# wireless_interface.net
KiCad netlist of a schematic drawn in EAGLE
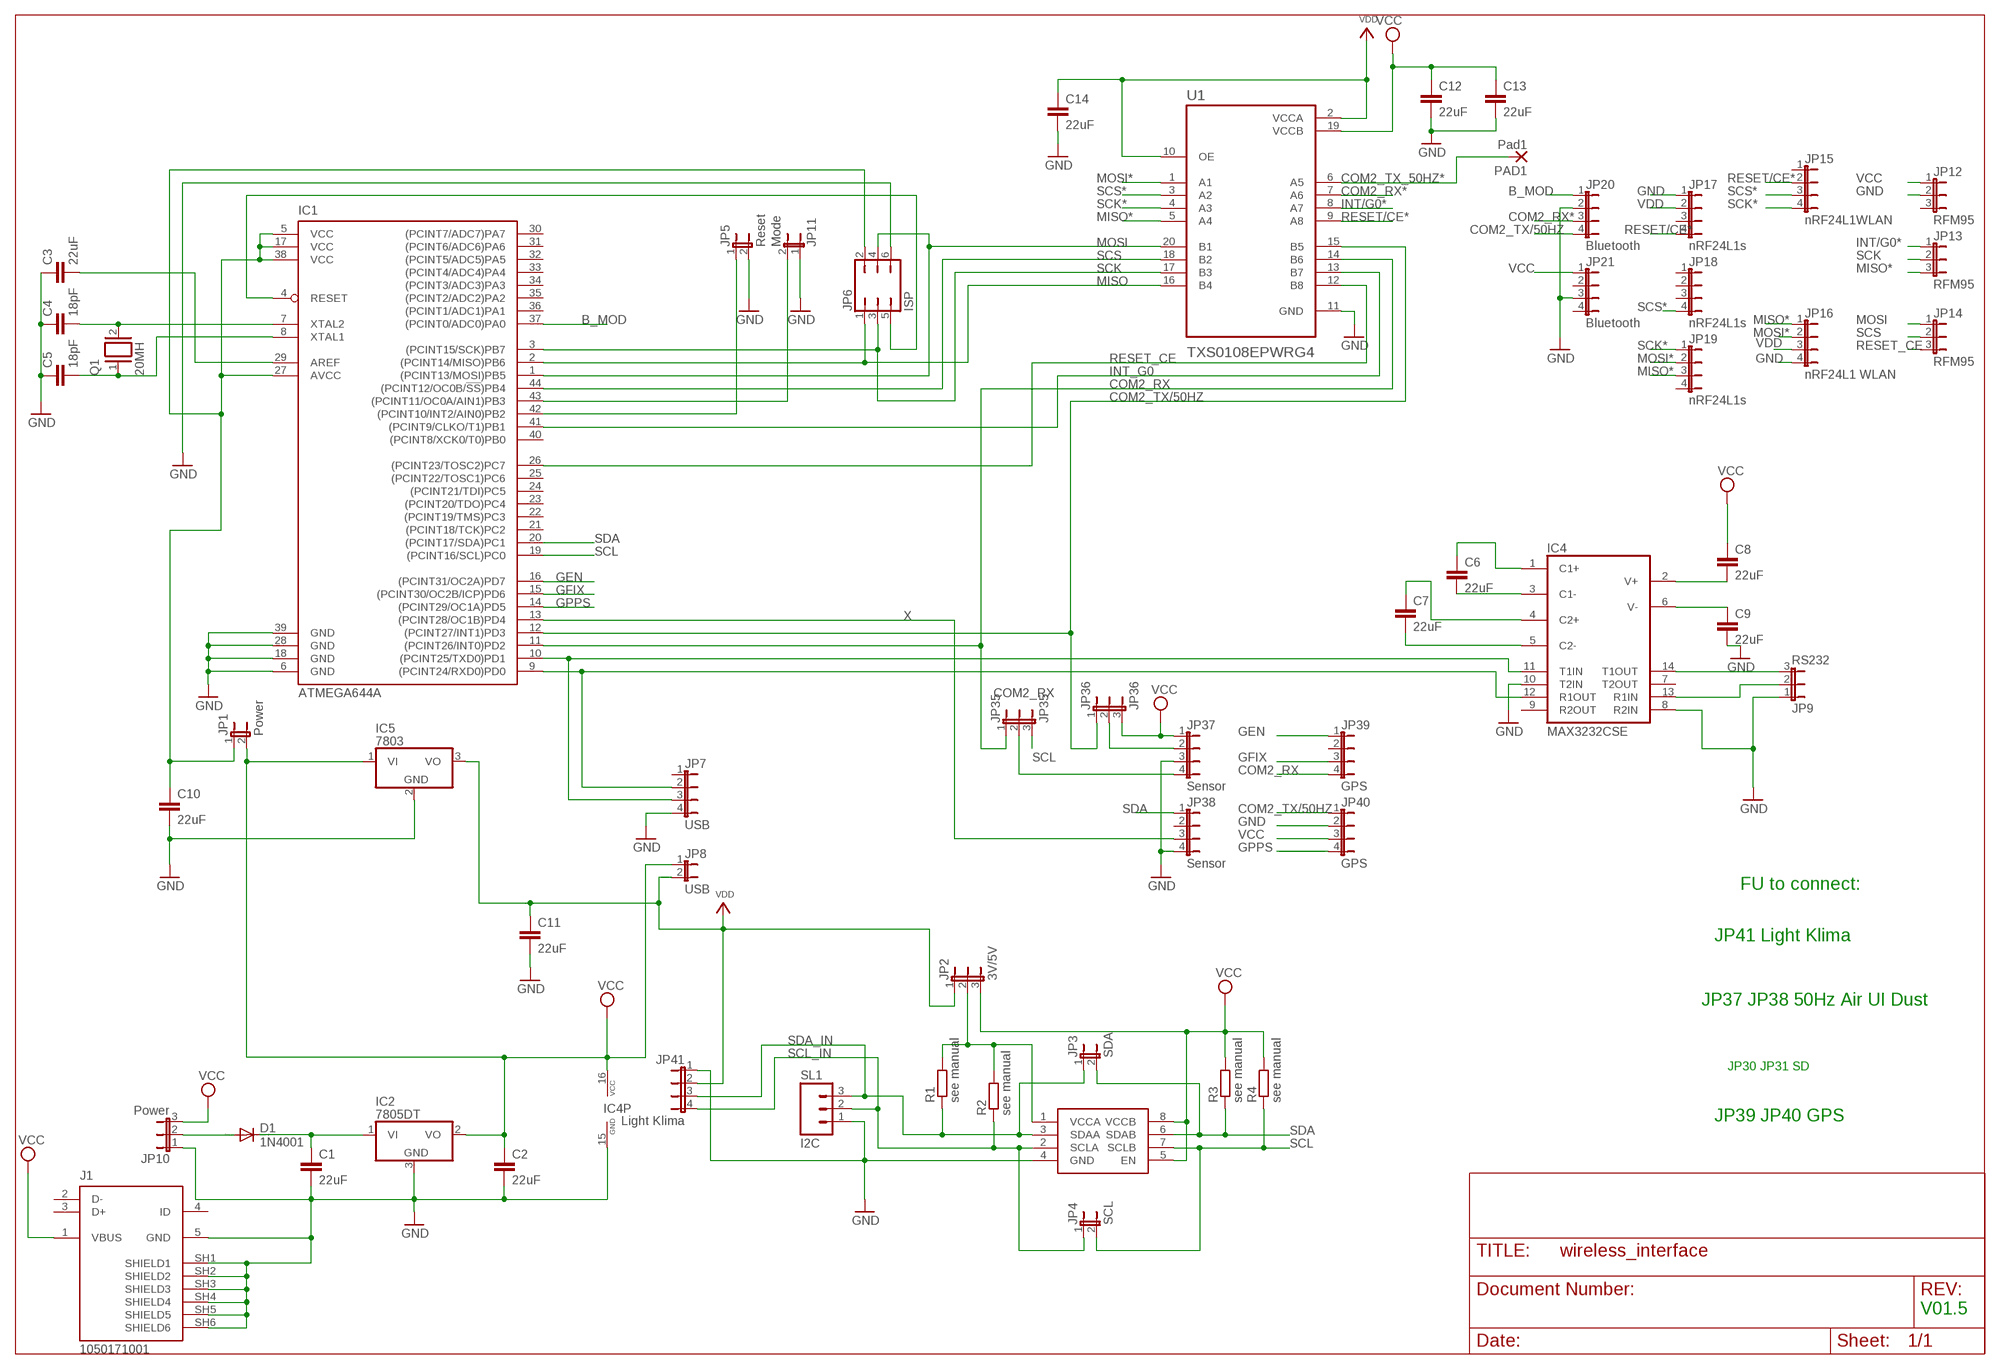
[diagram p0: schematic, sheet 1]

(export (version "E")
  (design (tool "Eeschema 10.0.6"))
  (components
    (comp (ref "C1")
      (value "22uF")
      (footprint "eagle-import:C1206")
      (libsource (lib "eagle-import") (part "C-EUC1206"))
    )
    (comp (ref "C2")
      (value "22uF")
      (footprint "eagle-import:C1206")
      (libsource (lib "eagle-import") (part "C-EUC1206"))
    )
    (comp (ref "C3")
      (value "22uF")
      (footprint "eagle-import:C1206")
      (libsource (lib "eagle-import") (part "C-EUC1206"))
    )
    (comp (ref "C4")
      (value "18pF")
      (footprint "eagle-import:C025-025X050")
      (libsource (lib "eagle-import") (part "resistor_C-EU025-025X050"))
    )
    (comp (ref "C5")
      (value "18pF")
      (footprint "eagle-import:C025-025X050")
      (libsource (lib "eagle-import") (part "resistor_C-EU025-025X050"))
    )
    (comp (ref "C6")
      (value "22uF")
      (footprint "eagle-import:C1206")
      (libsource (lib "eagle-import") (part "C-EUC1206"))
    )
    (comp (ref "C7")
      (value "22uF")
      (footprint "eagle-import:C1206")
      (libsource (lib "eagle-import") (part "C-EUC1206"))
    )
    (comp (ref "C8")
      (value "22uF")
      (footprint "eagle-import:C1206")
      (libsource (lib "eagle-import") (part "C-EUC1206"))
    )
    (comp (ref "C9")
      (value "22uF")
      (footprint "eagle-import:C1206")
      (libsource (lib "eagle-import") (part "C-EUC1206"))
    )
    (comp (ref "C10")
      (value "22uF")
      (footprint "eagle-import:C1206")
      (libsource (lib "eagle-import") (part "C-EUC1206"))
    )
    (comp (ref "C11")
      (value "22uF")
      (footprint "eagle-import:C1206")
      (libsource (lib "eagle-import") (part "C-EUC1206"))
    )
    (comp (ref "C12")
      (value "22uF")
      (footprint "eagle-import:C1206")
      (libsource (lib "eagle-import") (part "C-EUC1206"))
    )
    (comp (ref "C13")
      (value "22uF")
      (footprint "eagle-import:C1206")
      (libsource (lib "eagle-import") (part "C-EUC1206"))
    )
    (comp (ref "C14")
      (value "22uF")
      (footprint "eagle-import:C1206")
      (libsource (lib "eagle-import") (part "C-EUC1206"))
    )
    (comp (ref "D1")
      (value "1N4001")
      (footprint "eagle-import:SOD106-W")
      (libsource (lib "eagle-import") (part "DIODE-SOD106-W"))
    )
    (comp (ref "IC1")
      (value "ATMEGA644A")
      (footprint "eagle-import:TQFP44")
      (fields (field (name "MPN") "ATMEGA644PV-10AU"))
      (libsource (lib "eagle-import") (part "ATMEGA644A"))
    )
    (comp (ref "IC2")
      (value "7805DT")
      (footprint "eagle-import:TO252")
      (libsource (lib "eagle-import") (part "78DT05"))
    )
    (comp (ref "IC3")
      (value "PCA9517")
      (footprint "eagle-import:SO-08")
      (libsource (lib "eagle-import") (part "PCA9517"))
    )
    (comp (ref "IC4")
      (value "MAX3232CSE")
      (footprint "eagle-import:SO16")
      (libsource (lib "eagle-import") (part "MAX3232SEC"))
    )
    (comp (ref "IC5")
      (value "7803")
      (footprint "eagle-import:TO220V")
      (libsource (lib "eagle-import") (part "78TV05"))
    )
    (comp (ref "J1")
      (value "1050171001")
      (footprint "eagle-import:MOLEX_1050171001")
      (fields (field (name "MF") "Molex"))
      (libsource (lib "eagle-import") (part "1050171001"))
    )
    (comp (ref "JP1")
      (value "Power")
      (footprint "eagle-import:JP1")
      (libsource (lib "eagle-import") (part "JP1E"))
    )
    (comp (ref "JP2")
      (value "3V/5V")
      (footprint "eagle-import:JP2")
      (libsource (lib "eagle-import") (part "JP2E"))
    )
    (comp (ref "JP3")
      (value "SDA")
      (footprint "eagle-import:JP1")
      (libsource (lib "eagle-import") (part "JP1E"))
    )
    (comp (ref "JP4")
      (value "SCL")
      (footprint "eagle-import:JP1")
      (libsource (lib "eagle-import") (part "JP1E"))
    )
    (comp (ref "JP5")
      (value "Reset")
      (footprint "eagle-import:JP1")
      (libsource (lib "eagle-import") (part "JP1E"))
    )
    (comp (ref "JP6")
      (value "ISP")
      (footprint "eagle-import:JP3Q")
      (libsource (lib "eagle-import") (part "JP3Q"))
    )
    (comp (ref "JP7")
      (value "USB")
      (footprint "eagle-import:JP4")
      (libsource (lib "eagle-import") (part "JP4E"))
    )
    (comp (ref "JP8")
      (value "USB")
      (footprint "eagle-import:JP1")
      (libsource (lib "eagle-import") (part "JP1E"))
    )
    (comp (ref "JP9")
      (value "RS232")
      (footprint "eagle-import:JP2")
      (libsource (lib "eagle-import") (part "JP2E"))
    )
    (comp (ref "JP10")
      (value "Power")
      (footprint "eagle-import:JP2")
      (libsource (lib "eagle-import") (part "JP2E"))
    )
    (comp (ref "JP11")
      (value "Mode")
      (footprint "eagle-import:JP1")
      (libsource (lib "eagle-import") (part "JP1E"))
    )
    (comp (ref "JP12")
      (value "RFM95")
      (footprint "eagle-import:JP2")
      (libsource (lib "eagle-import") (part "JP2E"))
    )
    (comp (ref "JP13")
      (value "RFM95")
      (footprint "eagle-import:JP2")
      (libsource (lib "eagle-import") (part "JP2E"))
    )
    (comp (ref "JP14")
      (value "RFM95")
      (footprint "eagle-import:JP2")
      (libsource (lib "eagle-import") (part "JP2E"))
    )
    (comp (ref "JP15")
      (value "nRF24L1WLAN")
      (footprint "eagle-import:JP4")
      (libsource (lib "eagle-import") (part "JP4E"))
    )
    (comp (ref "JP16")
      (value "nRF24L1 WLAN")
      (footprint "eagle-import:JP4")
      (libsource (lib "eagle-import") (part "JP4E"))
    )
    (comp (ref "JP17")
      (value "nRF24L1s")
      (footprint "eagle-import:JP4")
      (libsource (lib "eagle-import") (part "JP4E"))
    )
    (comp (ref "JP18")
      (value "nRF24L1s")
      (footprint "eagle-import:JP4")
      (libsource (lib "eagle-import") (part "JP4E"))
    )
    (comp (ref "JP19")
      (value "nRF24L1s")
      (footprint "eagle-import:JP4")
      (libsource (lib "eagle-import") (part "JP4E"))
    )
    (comp (ref "JP20")
      (value "Bluetooth")
      (footprint "eagle-import:JP4")
      (libsource (lib "eagle-import") (part "JP4E"))
    )
    (comp (ref "JP21")
      (value "Bluetooth")
      (footprint "eagle-import:JP4")
      (libsource (lib "eagle-import") (part "JP4E"))
    )
    (comp (ref "JP35")
      (value "JP35")
      (footprint "eagle-import:JP2")
      (libsource (lib "eagle-import") (part "JP2E"))
    )
    (comp (ref "JP36")
      (value "JP36")
      (footprint "eagle-import:JP2")
      (libsource (lib "eagle-import") (part "JP2E"))
    )
    (comp (ref "JP37")
      (value "Sensor")
      (footprint "eagle-import:JP4")
      (libsource (lib "eagle-import") (part "JP4E"))
    )
    (comp (ref "JP38")
      (value "Sensor")
      (footprint "eagle-import:JP4")
      (libsource (lib "eagle-import") (part "JP4E"))
    )
    (comp (ref "JP39")
      (value "GPS")
      (footprint "eagle-import:JP4")
      (libsource (lib "eagle-import") (part "JP4E"))
    )
    (comp (ref "JP40")
      (value "GPS")
      (footprint "eagle-import:JP4")
      (libsource (lib "eagle-import") (part "JP4E"))
    )
    (comp (ref "JP41")
      (value "Light Klima")
      (footprint "eagle-import:JP4")
      (libsource (lib "eagle-import") (part "JP4E"))
    )
    (comp (ref "PAD1")
      (value "Pad1")
      (footprint "eagle-import:SMD1,27-2,54")
      (libsource (lib "eagle-import") (part "WIREPADSMD1,27-254"))
    )
    (comp (ref "Q1")
      (value "20MH")
      (footprint "eagle-import:QS")
      (libsource (lib "eagle-import") (part "XTAL/S"))
    )
    (comp (ref "R1")
      (value "see manual")
      (footprint "eagle-import:R1206")
      (libsource (lib "eagle-import") (part "R-EU_R1206"))
    )
    (comp (ref "R2")
      (value "see manual")
      (footprint "eagle-import:R1206")
      (libsource (lib "eagle-import") (part "R-EU_R1206"))
    )
    (comp (ref "R3")
      (value "see manual")
      (footprint "eagle-import:R1206")
      (libsource (lib "eagle-import") (part "R-EU_R1206"))
    )
    (comp (ref "R4")
      (value "see manual")
      (footprint "eagle-import:R1206")
      (libsource (lib "eagle-import") (part "R-EU_R1206"))
    )
    (comp (ref "SL1")
      (value "I2C")
      (footprint "eagle-import:03P")
      (libsource (lib "eagle-import") (part "M03"))
    )
    (comp (ref "U1")
      (value "TXS0108EPWRG4")
      (footprint "eagle-import:SOP65P640X120-20N")
      (fields (field (name "MF") "Texas Instruments"))
      (libsource (lib "eagle-import") (part "TXS0108EPWRG4"))
    )
  )
  (nets
    (net (code "1") (name "/B_MOD") (class "Default")
      (node (ref "IC1") (pin "37") (pinfunction "(PCINT0/ADC0)PA0_37") (pintype "bidirectional"))
      (node (ref "JP20") (pin "1") (pinfunction "1_1") (pintype "passive"))
    )
    (net (code "2") (name "/COM2_RX") (class "Default")
      (node (ref "IC1") (pin "11") (pinfunction "(PCINT26/INT0)PD2_11") (pintype "bidirectional"))
      (node (ref "JP35") (pin "1") (pinfunction "1_1") (pintype "passive"))
      (node (ref "JP39") (pin "4") (pinfunction "4_4") (pintype "passive"))
      (node (ref "U1") (pin "14") (pinfunction "B6_14") (pintype "bidirectional"))
    )
    (net (code "3") (name "/COM2_RX*") (class "Default")
      (node (ref "JP20") (pin "3") (pinfunction "3_3") (pintype "passive"))
      (node (ref "U1") (pin "7") (pinfunction "A6_7") (pintype "bidirectional"))
    )
    (net (code "4") (name "/COM2_TX_50HZ*") (class "Default")
      (node (ref "PAD1") (pin "1") (pinfunction "P_1") (pintype "passive"))
      (node (ref "U1") (pin "6") (pinfunction "A5_6") (pintype "bidirectional"))
    )
    (net (code "5") (name "/COM2_TX{slash}50HZ") (class "Default")
      (node (ref "IC1") (pin "12") (pinfunction "(PCINT27/INT1)PD3_12") (pintype "bidirectional"))
      (node (ref "JP20") (pin "4") (pinfunction "4_4") (pintype "passive"))
      (node (ref "JP36") (pin "1") (pinfunction "1_1") (pintype "passive"))
      (node (ref "JP40") (pin "1") (pinfunction "1_1") (pintype "passive"))
      (node (ref "U1") (pin "15") (pinfunction "B5_15") (pintype "bidirectional"))
    )
    (net (code "6") (name "/GEN") (class "Default")
      (node (ref "IC1") (pin "16") (pinfunction "(PCINT31/OC2A)PD7_16") (pintype "bidirectional"))
      (node (ref "JP39") (pin "1") (pinfunction "1_1") (pintype "passive"))
    )
    (net (code "7") (name "/GFIX") (class "Default")
      (node (ref "IC1") (pin "15") (pinfunction "(PCINT30/OC2B/ICP)PD6_15") (pintype "bidirectional"))
      (node (ref "JP39") (pin "3") (pinfunction "3_3") (pintype "passive"))
    )
    (net (code "8") (name "/GPPS") (class "Default")
      (node (ref "IC1") (pin "14") (pinfunction "(PCINT29/OC1A)PD5_14") (pintype "bidirectional"))
      (node (ref "JP40") (pin "4") (pinfunction "4_4") (pintype "passive"))
    )
    (net (code "9") (name "/INT_G0") (class "Default")
      (node (ref "IC1") (pin "41") (pinfunction "(PCINT9/CLKO/T1)PB1_41") (pintype "bidirectional"))
      (node (ref "U1") (pin "13") (pinfunction "B7_13") (pintype "bidirectional"))
    )
    (net (code "10") (name "/INT{slash}G0*") (class "Default")
      (node (ref "JP13") (pin "1") (pinfunction "1_1") (pintype "passive"))
      (node (ref "U1") (pin "8") (pinfunction "A7_8") (pintype "bidirectional"))
    )
    (net (code "11") (name "/MISO") (class "Default")
      (node (ref "IC1") (pin "2") (pinfunction "(PCINT14/MISO)PB6_2") (pintype "bidirectional"))
      (node (ref "JP6") (pin "1") (pinfunction "1_1") (pintype "passive"))
      (node (ref "U1") (pin "16") (pinfunction "B4_16") (pintype "bidirectional"))
    )
    (net (code "12") (name "/MISO*") (class "Default")
      (node (ref "JP13") (pin "3") (pinfunction "3_3") (pintype "passive"))
      (node (ref "JP16") (pin "1") (pinfunction "1_1") (pintype "passive"))
      (node (ref "JP19") (pin "3") (pinfunction "3_3") (pintype "passive"))
      (node (ref "U1") (pin "5") (pinfunction "A4_5") (pintype "bidirectional"))
    )
    (net (code "13") (name "/MOSI") (class "Default")
      (node (ref "IC1") (pin "1") (pinfunction "(PCINT13/MOSI)PB5_1") (pintype "bidirectional"))
      (node (ref "JP14") (pin "1") (pinfunction "1_1") (pintype "passive"))
      (node (ref "JP6") (pin "4") (pinfunction "4_4") (pintype "passive"))
      (node (ref "U1") (pin "20") (pinfunction "B1_20") (pintype "bidirectional"))
    )
    (net (code "14") (name "/MOSI*") (class "Default")
      (node (ref "JP16") (pin "2") (pinfunction "2_2") (pintype "passive"))
      (node (ref "JP19") (pin "2") (pinfunction "2_2") (pintype "passive"))
      (node (ref "U1") (pin "1") (pinfunction "A1_1") (pintype "bidirectional"))
    )
    (net (code "15") (name "/RESET_CE") (class "Default")
      (node (ref "IC1") (pin "26") (pinfunction "(PCINT23/TOSC2)PC7_26") (pintype "output"))
      (node (ref "JP14") (pin "3") (pinfunction "3_3") (pintype "passive"))
      (node (ref "U1") (pin "12") (pinfunction "B8_12") (pintype "bidirectional"))
    )
    (net (code "16") (name "/RESET{slash}CE*") (class "Default")
      (node (ref "JP15") (pin "2") (pinfunction "2_2") (pintype "passive"))
      (node (ref "JP17") (pin "4") (pinfunction "4_4") (pintype "passive"))
      (node (ref "U1") (pin "9") (pinfunction "A8_9") (pintype "bidirectional"))
    )
    (net (code "17") (name "/SCK") (class "Default")
      (node (ref "IC1") (pin "3") (pinfunction "(PCINT15/SCK)PB7_3") (pintype "bidirectional"))
      (node (ref "JP13") (pin "2") (pinfunction "2_2") (pintype "passive"))
      (node (ref "JP6") (pin "3") (pinfunction "3_3") (pintype "passive"))
      (node (ref "U1") (pin "17") (pinfunction "B3_17") (pintype "bidirectional"))
    )
    (net (code "18") (name "/SCK*") (class "Default")
      (node (ref "JP15") (pin "4") (pinfunction "4_4") (pintype "passive"))
      (node (ref "JP19") (pin "1") (pinfunction "1_1") (pintype "passive"))
      (node (ref "U1") (pin "4") (pinfunction "A3_4") (pintype "bidirectional"))
    )
    (net (code "19") (name "/SCL") (class "Default")
      (node (ref "IC1") (pin "19") (pinfunction "(PCINT16/SCL)PC0_19") (pintype "output"))
      (node (ref "IC3") (pin "7") (pinfunction "SCLB_7") (pintype "bidirectional"))
      (node (ref "JP35") (pin "3") (pinfunction "3_3") (pintype "passive"))
      (node (ref "JP4") (pin "2") (pinfunction "2_2") (pintype "passive"))
      (node (ref "R4") (pin "1") (pinfunction "1_1") (pintype "passive"))
    )
    (net (code "20") (name "/SCL_IN") (class "Default")
      (node (ref "IC3") (pin "2") (pinfunction "SCLA_2") (pintype "bidirectional"))
      (node (ref "JP4") (pin "1") (pinfunction "1_1") (pintype "passive"))
      (node (ref "JP41") (pin "4") (pinfunction "4_4") (pintype "passive"))
      (node (ref "R2") (pin "1") (pinfunction "1_1") (pintype "passive"))
      (node (ref "SL1") (pin "2") (pinfunction "2_2") (pintype "passive"))
    )
    (net (code "21") (name "/SCS") (class "Default")
      (node (ref "IC1") (pin "44") (pinfunction "(PCINT12/OC0B/~{SS})PB4_44") (pintype "bidirectional"))
      (node (ref "JP14") (pin "2") (pinfunction "2_2") (pintype "passive"))
      (node (ref "U1") (pin "18") (pinfunction "B2_18") (pintype "bidirectional"))
    )
    (net (code "22") (name "/SCS*") (class "Default")
      (node (ref "JP15") (pin "3") (pinfunction "3_3") (pintype "passive"))
      (node (ref "JP18") (pin "4") (pinfunction "4_4") (pintype "passive"))
      (node (ref "U1") (pin "3") (pinfunction "A2_3") (pintype "bidirectional"))
    )
    (net (code "23") (name "/SDA") (class "Default")
      (node (ref "IC1") (pin "20") (pinfunction "(PCINT17/SDA)PC1_20") (pintype "output"))
      (node (ref "IC3") (pin "6") (pinfunction "SDAB_6") (pintype "bidirectional"))
      (node (ref "JP3") (pin "2") (pinfunction "2_2") (pintype "passive"))
      (node (ref "JP38") (pin "1") (pinfunction "1_1") (pintype "passive"))
      (node (ref "R3") (pin "1") (pinfunction "1_1") (pintype "passive"))
    )
    (net (code "24") (name "/SDA_IN") (class "Default")
      (node (ref "IC3") (pin "3") (pinfunction "SDAA_3") (pintype "bidirectional"))
      (node (ref "JP3") (pin "1") (pinfunction "1_1") (pintype "passive"))
      (node (ref "JP41") (pin "3") (pinfunction "3_3") (pintype "passive"))
      (node (ref "R1") (pin "1") (pinfunction "1_1") (pintype "passive"))
      (node (ref "SL1") (pin "3") (pinfunction "3_3") (pintype "passive"))
    )
    (net (code "25") (name "/X") (class "Default")
      (node (ref "IC1") (pin "13") (pinfunction "(PCINT28/OC1B)PD4_13") (pintype "bidirectional"))
      (node (ref "JP38") (pin "3") (pinfunction "3_3") (pintype "passive"))
    )
    (net (code "26") (name "GND") (class "Default")
      (node (ref "C1") (pin "2") (pinfunction "2_2") (pintype "passive"))
      (node (ref "C10") (pin "2") (pinfunction "2_2") (pintype "passive"))
      (node (ref "C11") (pin "2") (pinfunction "2_2") (pintype "passive"))
      (node (ref "C12") (pin "2") (pinfunction "2_2") (pintype "passive"))
      (node (ref "C13") (pin "2") (pinfunction "2_2") (pintype "passive"))
      (node (ref "C14") (pin "2") (pinfunction "2_2") (pintype "passive"))
      (node (ref "C2") (pin "2") (pinfunction "2_2") (pintype "passive"))
      (node (ref "C3") (pin "1") (pinfunction "1_1") (pintype "passive"))
      (node (ref "C4") (pin "1") (pinfunction "1_1") (pintype "passive"))
      (node (ref "C5") (pin "1") (pinfunction "1_1") (pintype "passive"))
      (node (ref "C9") (pin "2") (pinfunction "2_2") (pintype "passive"))
      (node (ref "IC1") (pin "18") (pinfunction "GND_18") (pintype "power_in"))
      (node (ref "IC1") (pin "28") (pinfunction "GND_28") (pintype "power_in"))
      (node (ref "IC1") (pin "39") (pinfunction "GND_39") (pintype "power_in"))
      (node (ref "IC1") (pin "6") (pinfunction "GND_6") (pintype "power_in"))
      (node (ref "IC2") (pin "3") (pinfunction "GND_3") (pintype "passive"))
      (node (ref "IC3") (pin "4") (pinfunction "GND_4") (pintype "bidirectional"))
      (node (ref "IC4") (pin "10") (pinfunction "T2IN_10") (pintype "input"))
      (node (ref "IC4") (pin "15") (pinfunction "GND_15") (pintype "power_in"))
      (node (ref "IC4") (pin "8") (pinfunction "R2IN_8") (pintype "input"))
      (node (ref "IC5") (pin "2") (pinfunction "GND_2") (pintype "passive"))
      (node (ref "J1") (pin "5") (pinfunction "GND_5") (pintype "power_in"))
      (node (ref "J1") (pin "SH1") (pinfunction "SHIELD1_SH1") (pintype "passive"))
      (node (ref "J1") (pin "SH2") (pinfunction "SHIELD2_SH2") (pintype "passive"))
      (node (ref "J1") (pin "SH3") (pinfunction "SHIELD3_SH3") (pintype "passive"))
      (node (ref "J1") (pin "SH4") (pinfunction "SHIELD4_SH4") (pintype "passive"))
      (node (ref "J1") (pin "SH5") (pinfunction "SHIELD5_SH5") (pintype "passive"))
      (node (ref "J1") (pin "SH6") (pinfunction "SHIELD6_SH6") (pintype "passive"))
      (node (ref "JP10") (pin "1") (pinfunction "1_1") (pintype "passive"))
      (node (ref "JP11") (pin "1") (pinfunction "1_1") (pintype "passive"))
      (node (ref "JP12") (pin "2") (pinfunction "2_2") (pintype "passive"))
      (node (ref "JP16") (pin "4") (pinfunction "4_4") (pintype "passive"))
      (node (ref "JP17") (pin "1") (pinfunction "1_1") (pintype "passive"))
      (node (ref "JP20") (pin "2") (pinfunction "2_2") (pintype "passive"))
      (node (ref "JP21") (pin "3") (pinfunction "3_3") (pintype "passive"))
      (node (ref "JP37") (pin "3") (pinfunction "3_3") (pintype "passive"))
      (node (ref "JP38") (pin "4") (pinfunction "4_4") (pintype "passive"))
      (node (ref "JP40") (pin "2") (pinfunction "2_2") (pintype "passive"))
      (node (ref "JP41") (pin "1") (pinfunction "1_1") (pintype "passive"))
      (node (ref "JP5") (pin "2") (pinfunction "2_2") (pintype "passive"))
      (node (ref "JP6") (pin "6") (pinfunction "6_6") (pintype "passive"))
      (node (ref "JP7") (pin "4") (pinfunction "4_4") (pintype "passive"))
      (node (ref "JP9") (pin "1") (pinfunction "1_1") (pintype "passive"))
      (node (ref "SL1") (pin "1") (pinfunction "1_1") (pintype "passive"))
      (node (ref "U1") (pin "11") (pinfunction "GND_11") (pintype "power_in"))
    )
    (net (code "27") (name "Net-(D1-PadA)") (class "Default")
      (node (ref "D1") (pin "A") (pinfunction "A_A") (pintype "passive"))
      (node (ref "JP10") (pin "2") (pinfunction "2_2") (pintype "passive"))
    )
    (net (code "28") (name "Net-(IC1-(PCINT10{slash}INT2{slash}AIN0)PB2)") (class "Default")
      (node (ref "IC1") (pin "42") (pinfunction "(PCINT10/INT2/AIN0)PB2_42") (pintype "bidirectional"))
      (node (ref "JP5") (pin "1") (pinfunction "1_1") (pintype "passive"))
    )
    (net (code "29") (name "Net-(IC1-(PCINT11{slash}OC0A{slash}AIN1)PB3)") (class "Default")
      (node (ref "IC1") (pin "43") (pinfunction "(PCINT11/OC0A/AIN1)PB3_43") (pintype "bidirectional"))
      (node (ref "JP11") (pin "2") (pinfunction "2_2") (pintype "passive"))
    )
    (net (code "30") (name "Net-(IC1-(PCINT24{slash}RXD0)PD0)") (class "Default")
      (node (ref "IC1") (pin "9") (pinfunction "(PCINT24/RXD0)PD0_9") (pintype "bidirectional"))
      (node (ref "IC4") (pin "12") (pinfunction "R1OUT_12") (pintype "output"))
      (node (ref "JP7") (pin "2") (pinfunction "2_2") (pintype "passive"))
    )
    (net (code "31") (name "Net-(IC1-(PCINT25{slash}TXD0)PD1)") (class "Default")
      (node (ref "IC1") (pin "10") (pinfunction "(PCINT25/TXD0)PD1_10") (pintype "bidirectional"))
      (node (ref "IC4") (pin "11") (pinfunction "T1IN_11") (pintype "input"))
      (node (ref "JP7") (pin "3") (pinfunction "3_3") (pintype "passive"))
    )
    (net (code "32") (name "Net-(IC1-AREF)") (class "Default")
      (node (ref "C3") (pin "2") (pinfunction "2_2") (pintype "passive"))
      (node (ref "IC1") (pin "29") (pinfunction "AREF_29") (pintype "passive"))
    )
    (net (code "33") (name "Net-(IC1-AVCC)") (class "Default")
      (node (ref "C10") (pin "1") (pinfunction "1_1") (pintype "passive"))
      (node (ref "IC1") (pin "17") (pinfunction "VCC_17") (pintype "power_in"))
      (node (ref "IC1") (pin "27") (pinfunction "AVCC_27") (pintype "power_in"))
      (node (ref "IC1") (pin "38") (pinfunction "VCC_38") (pintype "power_in"))
      (node (ref "IC1") (pin "5") (pinfunction "VCC_5") (pintype "power_in"))
      (node (ref "JP1") (pin "1") (pinfunction "1_1") (pintype "passive"))
      (node (ref "JP6") (pin "2") (pinfunction "2_2") (pintype "passive"))
    )
    (net (code "34") (name "Net-(IC1-RESET)") (class "Default")
      (node (ref "IC1") (pin "4") (pinfunction "RESET_4") (pintype "input"))
      (node (ref "JP6") (pin "5") (pinfunction "5_5") (pintype "passive"))
    )
    (net (code "35") (name "Net-(IC1-XTAL1)") (class "Default")
      (node (ref "C5") (pin "2") (pinfunction "2_2") (pintype "passive"))
      (node (ref "IC1") (pin "8") (pinfunction "XTAL1_8") (pintype "bidirectional"))
      (node (ref "Q1") (pin "1") (pinfunction "1_1") (pintype "passive"))
    )
    (net (code "36") (name "Net-(IC1-XTAL2)") (class "Default")
      (node (ref "C4") (pin "2") (pinfunction "2_2") (pintype "passive"))
      (node (ref "IC1") (pin "7") (pinfunction "XTAL2_7") (pintype "bidirectional"))
      (node (ref "Q1") (pin "2") (pinfunction "2_2") (pintype "passive"))
    )
    (net (code "37") (name "Net-(IC2-VI)") (class "Default")
      (node (ref "C1") (pin "1") (pinfunction "1_1") (pintype "passive"))
      (node (ref "D1") (pin "C") (pinfunction "C_C") (pintype "passive"))
      (node (ref "IC2") (pin "1") (pinfunction "VI_1") (pintype "input"))
    )
    (net (code "38") (name "Net-(IC3-VCCA)") (class "Default")
      (node (ref "IC3") (pin "1") (pinfunction "VCCA_1") (pintype "bidirectional"))
      (node (ref "JP2") (pin "2") (pinfunction "2_2") (pintype "passive"))
      (node (ref "R1") (pin "2") (pinfunction "2_2") (pintype "passive"))
      (node (ref "R2") (pin "2") (pinfunction "2_2") (pintype "passive"))
    )
    (net (code "39") (name "Net-(IC4A-C1+)") (class "Default")
      (node (ref "C6") (pin "1") (pinfunction "1_1") (pintype "passive"))
      (node (ref "IC4") (pin "1") (pinfunction "C1+_1") (pintype "bidirectional"))
    )
    (net (code "40") (name "Net-(IC4A-C1-)") (class "Default")
      (node (ref "C6") (pin "2") (pinfunction "2_2") (pintype "passive"))
      (node (ref "IC4") (pin "3") (pinfunction "C1-_3") (pintype "bidirectional"))
    )
    (net (code "41") (name "Net-(IC4A-C2+)") (class "Default")
      (node (ref "C7") (pin "1") (pinfunction "1_1") (pintype "passive"))
      (node (ref "IC4") (pin "4") (pinfunction "C2+_4") (pintype "bidirectional"))
    )
    (net (code "42") (name "Net-(IC4A-C2-)") (class "Default")
      (node (ref "C7") (pin "2") (pinfunction "2_2") (pintype "passive"))
      (node (ref "IC4") (pin "5") (pinfunction "C2-_5") (pintype "bidirectional"))
    )
    (net (code "43") (name "Net-(IC4A-R1IN)") (class "Default")
      (node (ref "IC4") (pin "13") (pinfunction "R1IN_13") (pintype "input"))
      (node (ref "JP9") (pin "2") (pinfunction "2_2") (pintype "passive"))
    )
    (net (code "44") (name "Net-(IC4A-T1OUT)") (class "Default")
      (node (ref "IC4") (pin "14") (pinfunction "T1OUT_14") (pintype "output"))
      (node (ref "JP9") (pin "3") (pinfunction "3_3") (pintype "passive"))
    )
    (net (code "45") (name "Net-(IC4A-V+)") (class "Default")
      (node (ref "C8") (pin "2") (pinfunction "2_2") (pintype "passive"))
      (node (ref "IC4") (pin "2") (pinfunction "V+_2") (pintype "bidirectional"))
    )
    (net (code "46") (name "Net-(IC4A-V-)") (class "Default")
      (node (ref "C9") (pin "1") (pinfunction "1_1") (pintype "passive"))
      (node (ref "IC4") (pin "6") (pinfunction "V-_6") (pintype "bidirectional"))
    )
    (net (code "47") (name "Net-(JP35-Pad2)") (class "Default")
      (node (ref "JP35") (pin "2") (pinfunction "2_2") (pintype "passive"))
      (node (ref "JP37") (pin "4") (pinfunction "4_4") (pintype "passive"))
    )
    (net (code "48") (name "Net-(JP36-Pad2)") (class "Default")
      (node (ref "JP36") (pin "2") (pinfunction "2_2") (pintype "passive"))
      (node (ref "JP37") (pin "2") (pinfunction "2_2") (pintype "passive"))
    )
    (net (code "49") (name "VCC") (class "Default")
      (node (ref "C12") (pin "1") (pinfunction "1_1") (pintype "passive"))
      (node (ref "C13") (pin "1") (pinfunction "1_1") (pintype "passive"))
      (node (ref "C2") (pin "1") (pinfunction "1_1") (pintype "passive"))
      (node (ref "C8") (pin "1") (pinfunction "1_1") (pintype "passive"))
      (node (ref "IC2") (pin "2") (pinfunction "VO_2") (pintype "passive"))
      (node (ref "IC3") (pin "5") (pinfunction "EN_5") (pintype "bidirectional"))
      (node (ref "IC3") (pin "8") (pinfunction "VCCB_8") (pintype "bidirectional"))
      (node (ref "IC4") (pin "16") (pinfunction "VCC_16") (pintype "power_in"))
      (node (ref "IC5") (pin "1") (pinfunction "VI_1") (pintype "input"))
      (node (ref "J1") (pin "1") (pinfunction "VBUS_1") (pintype "power_in"))
      (node (ref "JP1") (pin "2") (pinfunction "2_2") (pintype "passive"))
      (node (ref "JP10") (pin "3") (pinfunction "3_3") (pintype "passive"))
      (node (ref "JP12") (pin "1") (pinfunction "1_1") (pintype "passive"))
      (node (ref "JP2") (pin "3") (pinfunction "3_3") (pintype "passive"))
      (node (ref "JP21") (pin "1") (pinfunction "1_1") (pintype "passive"))
      (node (ref "JP36") (pin "3") (pinfunction "3_3") (pintype "passive"))
      (node (ref "JP37") (pin "1") (pinfunction "1_1") (pintype "passive"))
      (node (ref "JP40") (pin "3") (pinfunction "3_3") (pintype "passive"))
      (node (ref "JP8") (pin "1") (pinfunction "1_1") (pintype "passive"))
      (node (ref "R3") (pin "2") (pinfunction "2_2") (pintype "passive"))
      (node (ref "R4") (pin "2") (pinfunction "2_2") (pintype "passive"))
      (node (ref "U1") (pin "19") (pinfunction "VCCB_19") (pintype "power_in"))
    )
    (net (code "50") (name "VDD") (class "Default")
      (node (ref "C11") (pin "1") (pinfunction "1_1") (pintype "passive"))
      (node (ref "C14") (pin "1") (pinfunction "1_1") (pintype "passive"))
      (node (ref "IC5") (pin "3") (pinfunction "VO_3") (pintype "passive"))
      (node (ref "JP16") (pin "3") (pinfunction "3_3") (pintype "passive"))
      (node (ref "JP17") (pin "2") (pinfunction "2_2") (pintype "passive"))
      (node (ref "JP2") (pin "1") (pinfunction "1_1") (pintype "passive"))
      (node (ref "JP41") (pin "2") (pinfunction "2_2") (pintype "passive"))
      (node (ref "JP8") (pin "2") (pinfunction "2_2") (pintype "passive"))
      (node (ref "U1") (pin "10") (pinfunction "OE_10") (pintype "input"))
      (node (ref "U1") (pin "2") (pinfunction "VCCA_2") (pintype "power_in"))
    )
    (net (code "51") (name "unconnected-(IC1-(PCINT1{slash}ADC1)PA1-Pad36)") (class "Default")
      (node (ref "IC1") (pin "36") (pinfunction "(PCINT1/ADC1)PA1_36") (pintype "bidirectional"))
    )
    (net (code "52") (name "unconnected-(IC1-(PCINT2{slash}ADC2)PA2-Pad35)") (class "Default")
      (node (ref "IC1") (pin "35") (pinfunction "(PCINT2/ADC2)PA2_35") (pintype "bidirectional"))
    )
    (net (code "53") (name "unconnected-(IC1-(PCINT3{slash}ADC3)PA3-Pad34)") (class "Default")
      (node (ref "IC1") (pin "34") (pinfunction "(PCINT3/ADC3)PA3_34") (pintype "bidirectional"))
    )
    (net (code "54") (name "unconnected-(IC1-(PCINT4{slash}ADC4)PA4-Pad33)") (class "Default")
      (node (ref "IC1") (pin "33") (pinfunction "(PCINT4/ADC4)PA4_33") (pintype "bidirectional"))
    )
    (net (code "55") (name "unconnected-(IC1-(PCINT5{slash}ADC5)PA5-Pad32)") (class "Default")
      (node (ref "IC1") (pin "32") (pinfunction "(PCINT5/ADC5)PA5_32") (pintype "bidirectional"))
    )
    (net (code "56") (name "unconnected-(IC1-(PCINT6{slash}ADC6)PA6-Pad31)") (class "Default")
      (node (ref "IC1") (pin "31") (pinfunction "(PCINT6/ADC6)PA6_31") (pintype "bidirectional"))
    )
    (net (code "57") (name "unconnected-(IC1-(PCINT7{slash}ADC7)PA7-Pad30)") (class "Default")
      (node (ref "IC1") (pin "30") (pinfunction "(PCINT7/ADC7)PA7_30") (pintype "bidirectional"))
    )
    (net (code "58") (name "unconnected-(IC1-(PCINT8{slash}XCK0{slash}T0)PB0-Pad40)") (class "Default")
      (node (ref "IC1") (pin "40") (pinfunction "(PCINT8/XCK0/T0)PB0_40") (pintype "bidirectional"))
    )
    (net (code "59") (name "unconnected-(IC1-(PCINT18{slash}TCK)PC2-Pad21)") (class "Default")
      (node (ref "IC1") (pin "21") (pinfunction "(PCINT18/TCK)PC2_21") (pintype "output"))
    )
    (net (code "60") (name "unconnected-(IC1-(PCINT19{slash}TMS)PC3-Pad22)") (class "Default")
      (node (ref "IC1") (pin "22") (pinfunction "(PCINT19/TMS)PC3_22") (pintype "output"))
    )
    (net (code "61") (name "unconnected-(IC1-(PCINT20{slash}TDO)PC4-Pad23)") (class "Default")
      (node (ref "IC1") (pin "23") (pinfunction "(PCINT20/TDO)PC4_23") (pintype "output"))
    )
    (net (code "62") (name "unconnected-(IC1-(PCINT21{slash}TDI)PC5-Pad24)") (class "Default")
      (node (ref "IC1") (pin "24") (pinfunction "(PCINT21/TDI)PC5_24") (pintype "output"))
    )
    (net (code "63") (name "unconnected-(IC1-(PCINT22{slash}TOSC1)PC6-Pad25)") (class "Default")
      (node (ref "IC1") (pin "25") (pinfunction "(PCINT22/TOSC1)PC6_25") (pintype "output"))
    )
    (net (code "64") (name "unconnected-(IC4A-R2OUT-Pad9)") (class "Default")
      (node (ref "IC4") (pin "9") (pinfunction "R2OUT_9") (pintype "output"))
    )
    (net (code "65") (name "unconnected-(IC4A-T2OUT-Pad7)") (class "Default")
      (node (ref "IC4") (pin "7") (pinfunction "T2OUT_7") (pintype "output"))
    )
    (net (code "66") (name "unconnected-(J1-D+-Pad3)") (class "Default")
      (node (ref "J1") (pin "3") (pinfunction "D+_3") (pintype "bidirectional"))
    )
    (net (code "67") (name "unconnected-(J1-D--Pad2)") (class "Default")
      (node (ref "J1") (pin "2") (pinfunction "D-_2") (pintype "bidirectional"))
    )
    (net (code "68") (name "unconnected-(J1-ID-Pad4)") (class "Default")
      (node (ref "J1") (pin "4") (pinfunction "ID_4") (pintype "bidirectional"))
    )
    (net (code "69") (name "unconnected-(JP7-Pad1)") (class "Default")
      (node (ref "JP7") (pin "1") (pinfunction "1_1") (pintype "passive"))
    )
    (net (code "70") (name "unconnected-(JP12-Pad3)") (class "Default")
      (node (ref "JP12") (pin "3") (pinfunction "3_3") (pintype "passive"))
    )
    (net (code "71") (name "unconnected-(JP15-Pad1)") (class "Default")
      (node (ref "JP15") (pin "1") (pinfunction "1_1") (pintype "passive"))
    )
    (net (code "72") (name "unconnected-(JP17-Pad3)") (class "Default")
      (node (ref "JP17") (pin "3") (pinfunction "3_3") (pintype "passive"))
    )
    (net (code "73") (name "unconnected-(JP18-Pad1)") (class "Default")
      (node (ref "JP18") (pin "1") (pinfunction "1_1") (pintype "passive"))
    )
    (net (code "74") (name "unconnected-(JP18-Pad2)") (class "Default")
      (node (ref "JP18") (pin "2") (pinfunction "2_2") (pintype "passive"))
    )
    (net (code "75") (name "unconnected-(JP18-Pad3)") (class "Default")
      (node (ref "JP18") (pin "3") (pinfunction "3_3") (pintype "passive"))
    )
    (net (code "76") (name "unconnected-(JP19-Pad4)") (class "Default")
      (node (ref "JP19") (pin "4") (pinfunction "4_4") (pintype "passive"))
    )
    (net (code "77") (name "unconnected-(JP21-Pad2)") (class "Default")
      (node (ref "JP21") (pin "2") (pinfunction "2_2") (pintype "passive"))
    )
    (net (code "78") (name "unconnected-(JP21-Pad4)") (class "Default")
      (node (ref "JP21") (pin "4") (pinfunction "4_4") (pintype "passive"))
    )
    (net (code "79") (name "unconnected-(JP38-Pad2)") (class "Default")
      (node (ref "JP38") (pin "2") (pinfunction "2_2") (pintype "passive"))
    )
    (net (code "80") (name "unconnected-(JP39-Pad2)") (class "Default")
      (node (ref "JP39") (pin "2") (pinfunction "2_2") (pintype "passive"))
    )
  )
)
